# nRF9160_Thing_Plus.net
KiCad netlist of a schematic drawn in EAGLE
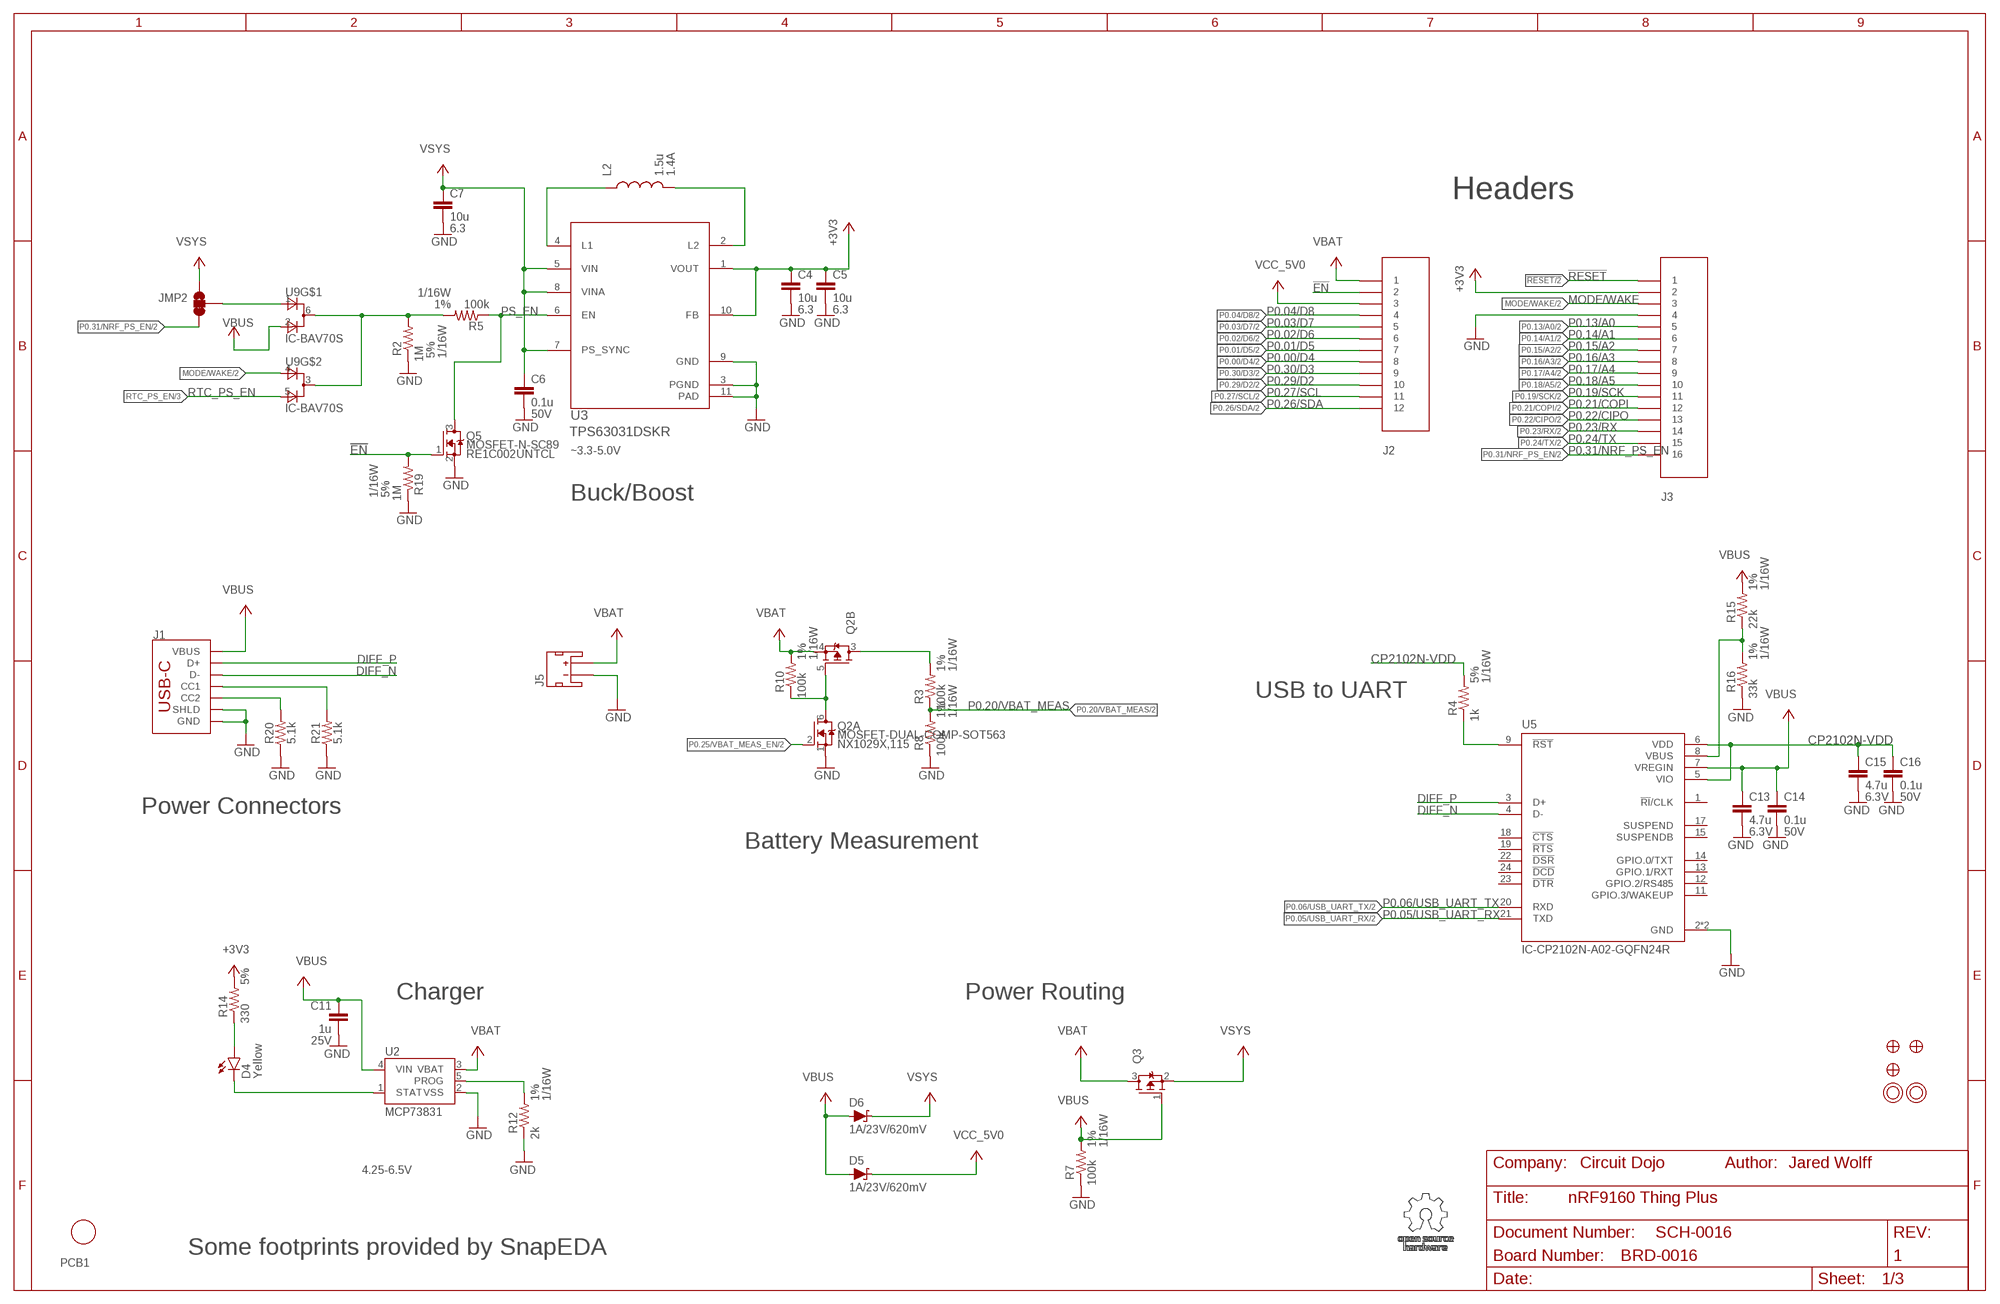
[diagram p0: schematic, sheet 1]
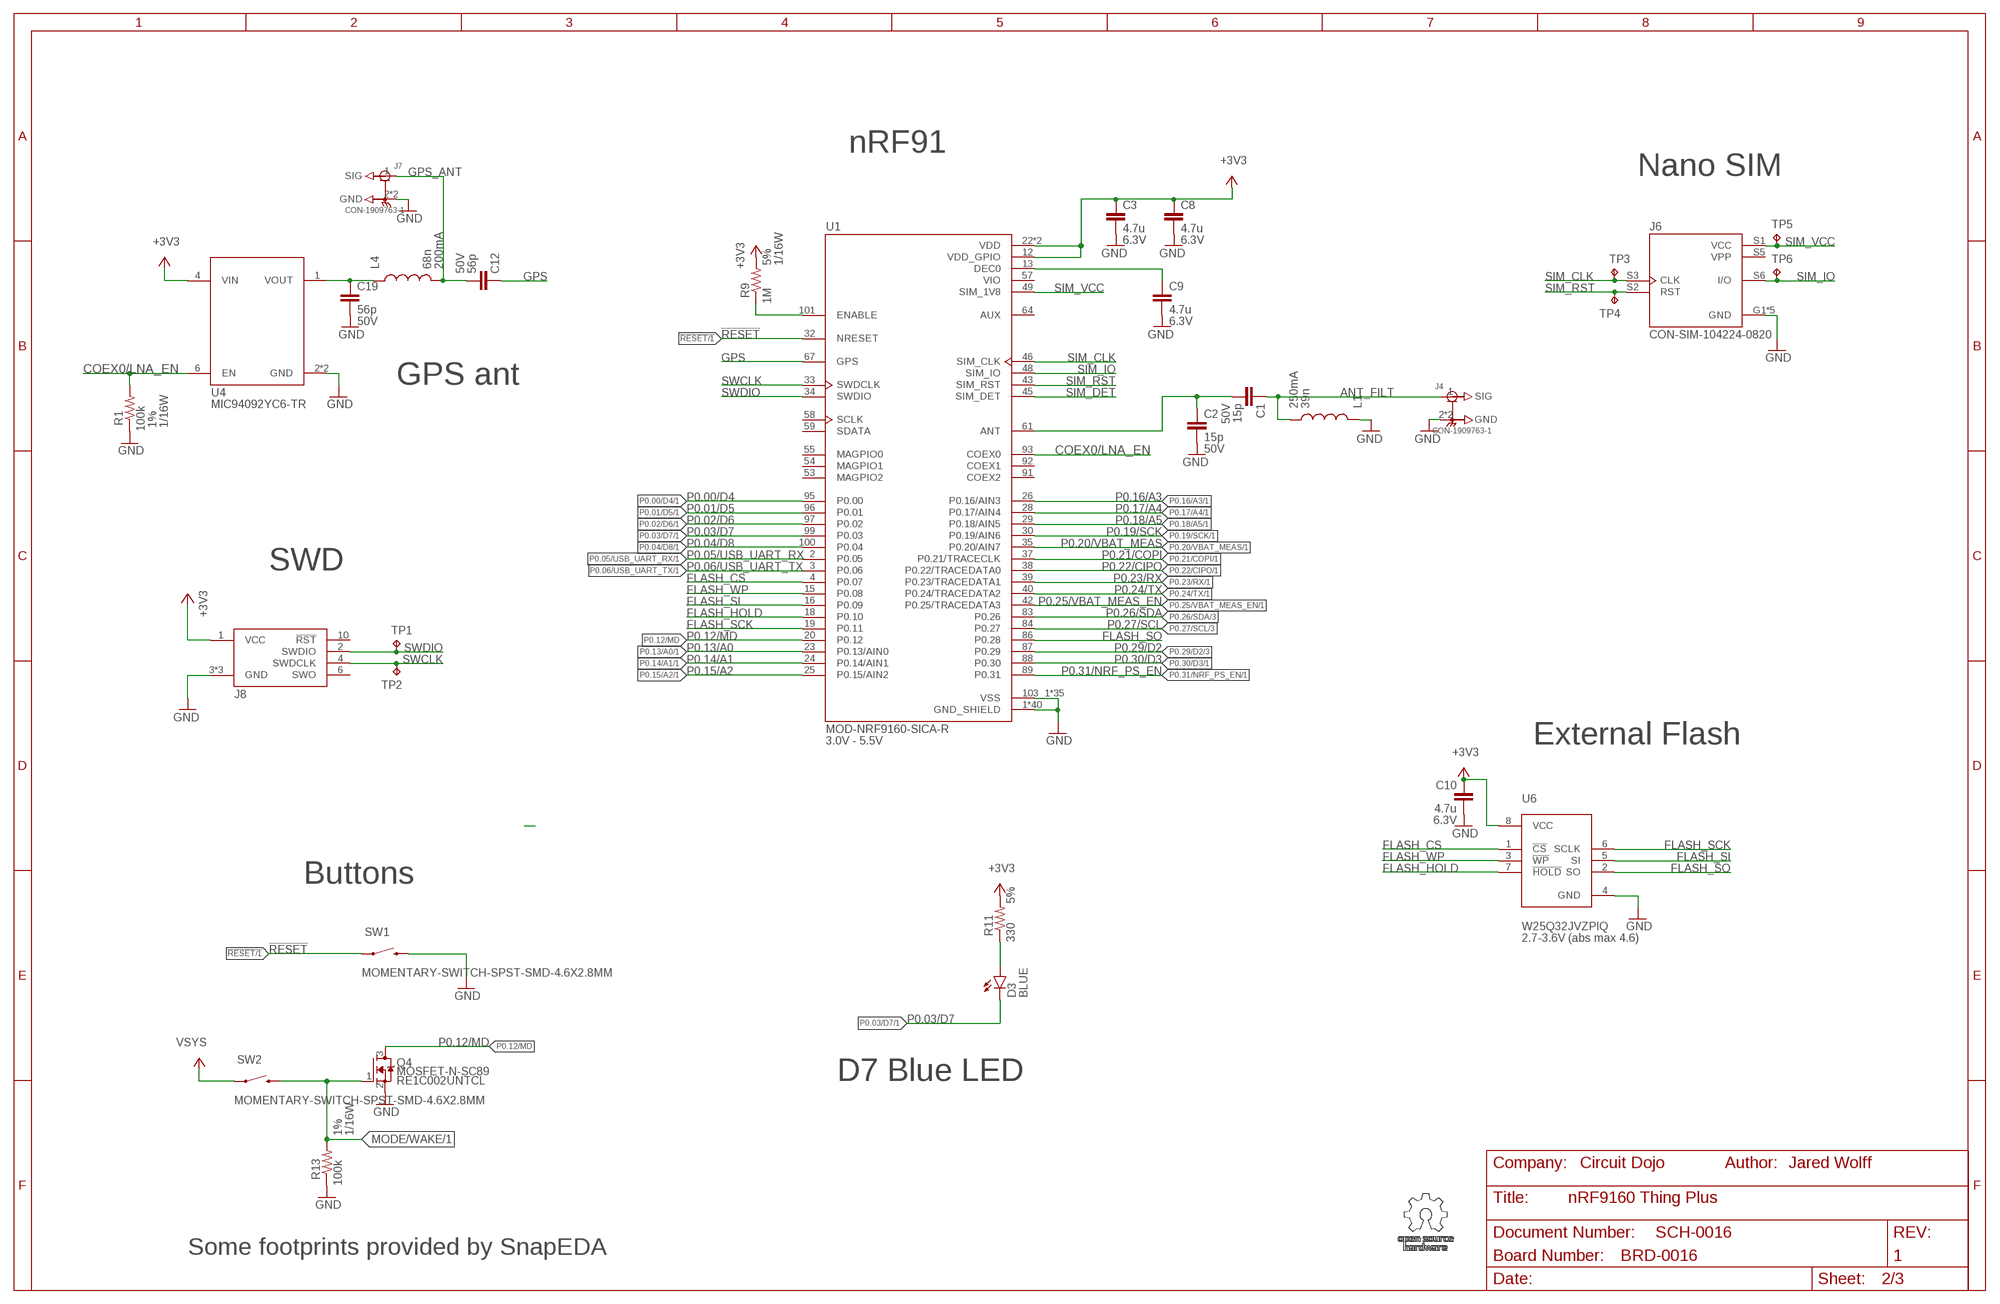
[diagram p1: schematic, sheet 2]
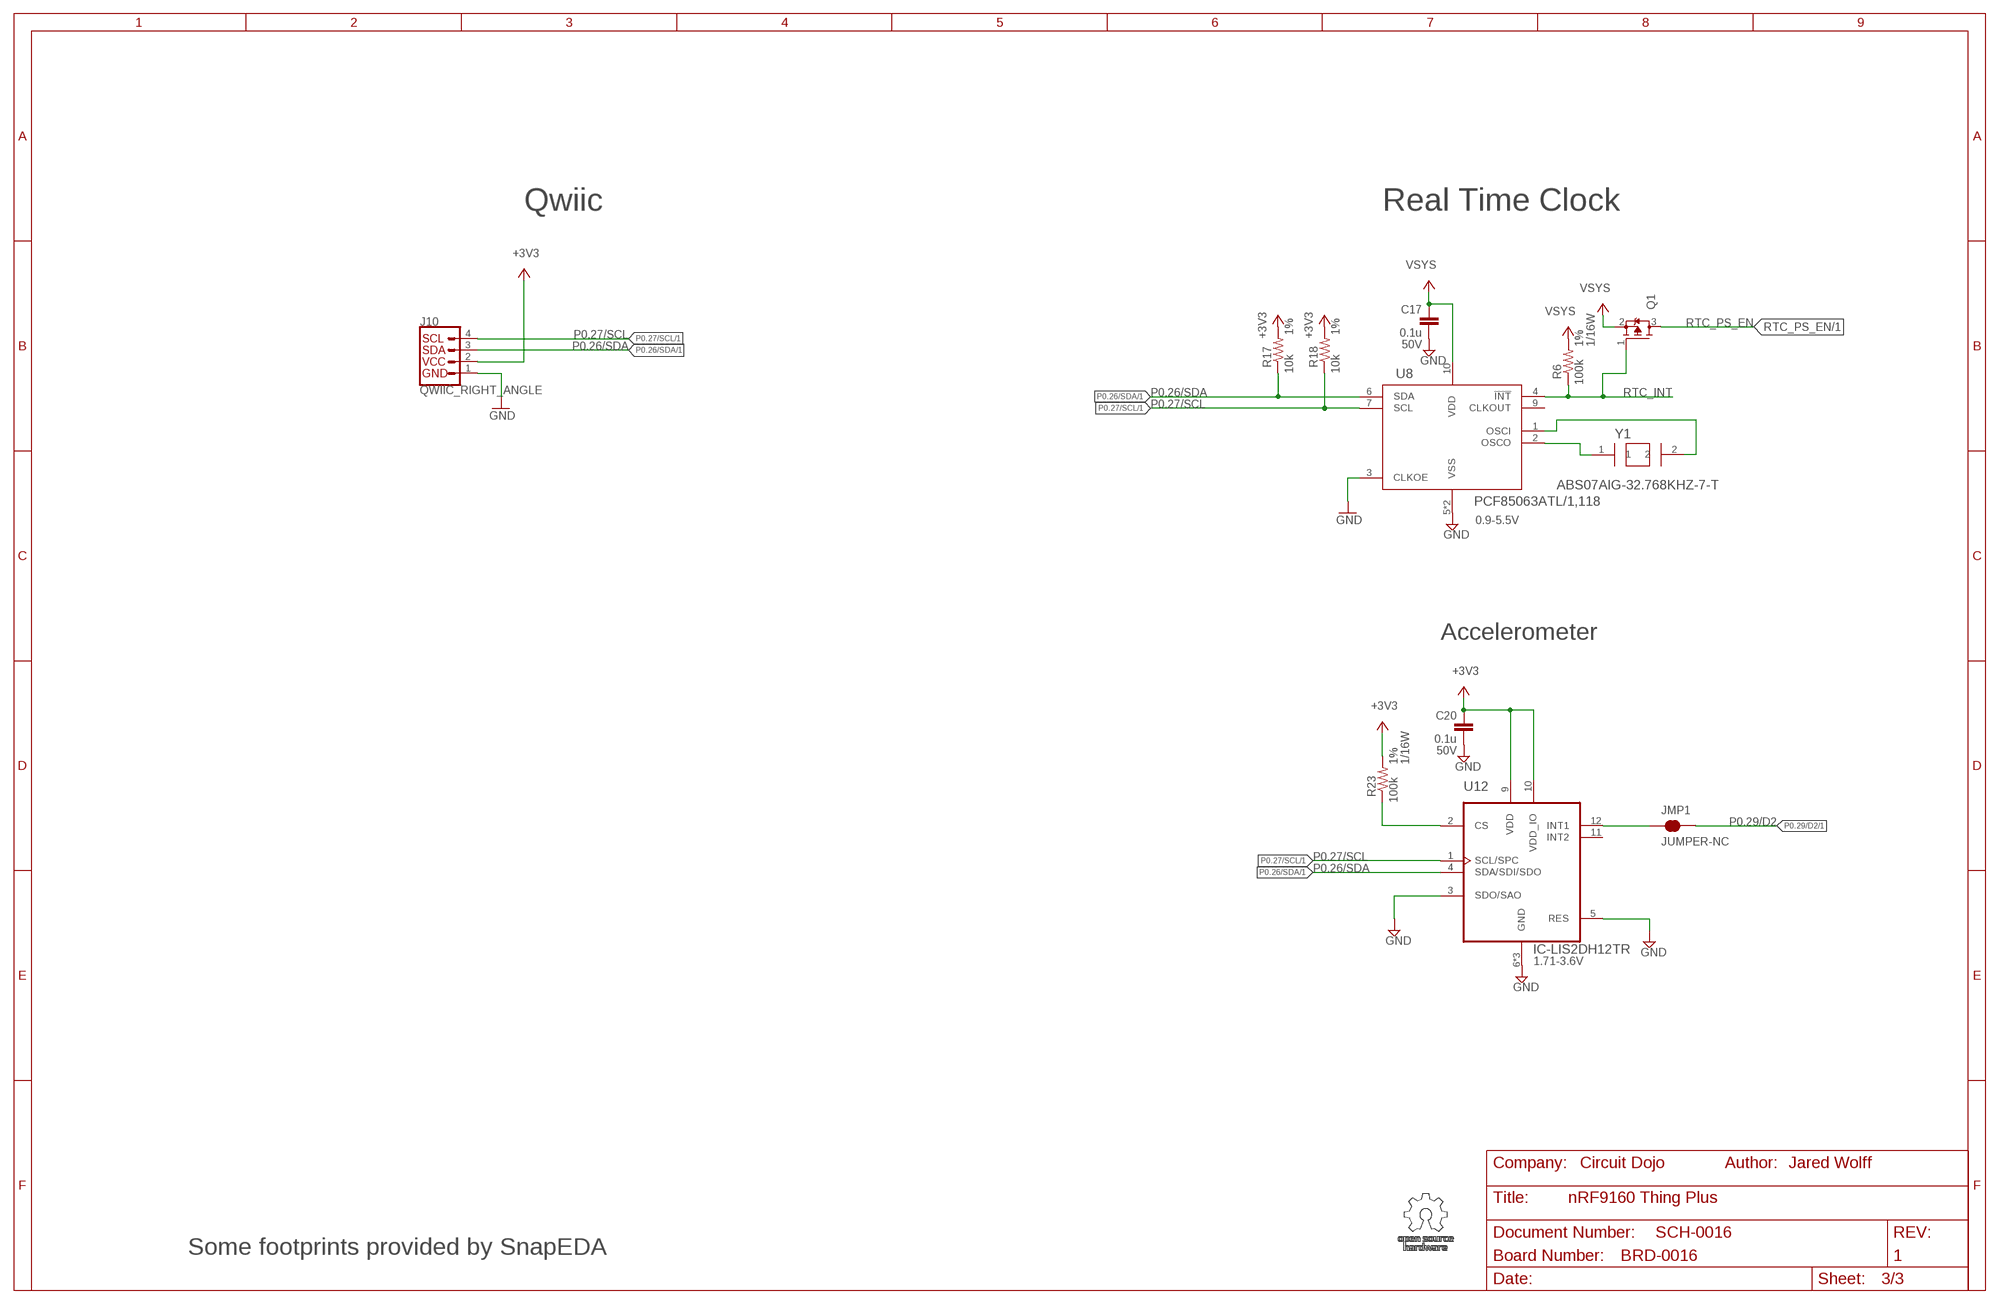
[diagram p2: schematic, sheet 3]

(export (version "E")
  (design (tool "Eeschema 10.0.6"))
  (components
    (comp (ref "C4")
      (value "10u")
      (footprint "eagle-import:C0603")
      (fields (field (name "MPN") "JMK107ABJ106MA-T") (field (name "VOLTHIGH") "6.3"))
      (libsource (lib "eagle-import") (part "CAP-0603-10U-6.3V"))
    )
    (comp (ref "C5")
      (value "10u")
      (footprint "eagle-import:C0603")
      (fields (field (name "MPN") "JMK107ABJ106MA-T") (field (name "VOLTHIGH") "6.3"))
      (libsource (lib "eagle-import") (part "CAP-0603-10U-6.3V"))
    )
    (comp (ref "C6")
      (value "0.1u")
      (footprint "eagle-import:CAPC1005X55N")
      (fields
        (field (name "MF") "Taiyo Yuden")
        (field (name "MPN") "UMK105BJ104KV-F")
        (field (name "VOLTHIGH") "50V")
      )
      (libsource (lib "eagle-import") (part "CAP-0402-0.1U-50V"))
    )
    (comp (ref "C7")
      (value "10u")
      (footprint "eagle-import:C0603")
      (fields (field (name "MPN") "JMK107ABJ106MA-T") (field (name "VOLTHIGH") "6.3"))
      (libsource (lib "eagle-import") (part "CAP-0603-10U-6.3V"))
    )
    (comp (ref "C11")
      (value "1u")
      (footprint "eagle-import:CAPC1005X55N")
      (fields
        (field (name "MF") "TDK")
        (field (name "MPN") "C1005X5R1E105M050BC")
        (field (name "VOLTHIGH") "25V")
      )
      (libsource (lib "eagle-import") (part "CAP-0402-1U-25V-1"))
    )
    (comp (ref "C13")
      (value "4.7u")
      (footprint "eagle-import:C0603")
      (fields (field (name "MPN") "JMK107BB7475MA-T") (field (name "VOLTHIGH") "6.3V"))
      (libsource (lib "eagle-import") (part "CAP-0603-4.7U-6.3V-2"))
    )
    (comp (ref "C14")
      (value "0.1u")
      (footprint "eagle-import:CAPC1005X55N")
      (fields
        (field (name "MF") "Taiyo Yuden")
        (field (name "MPN") "UMK105BJ104KV-F")
        (field (name "VOLTHIGH") "50V")
      )
      (libsource (lib "eagle-import") (part "CAP-0402-0.1U-50V"))
    )
    (comp (ref "C15")
      (value "4.7u")
      (footprint "eagle-import:C0603")
      (fields (field (name "MPN") "JMK107BB7475MA-T") (field (name "VOLTHIGH") "6.3V"))
      (libsource (lib "eagle-import") (part "CAP-0603-4.7U-6.3V-2"))
    )
    (comp (ref "C16")
      (value "0.1u")
      (footprint "eagle-import:CAPC1005X55N")
      (fields
        (field (name "MF") "Taiyo Yuden")
        (field (name "MPN") "UMK105BJ104KV-F")
        (field (name "VOLTHIGH") "50V")
      )
      (libsource (lib "eagle-import") (part "CAP-0402-0.1U-50V"))
    )
    (comp (ref "D4")
      (value "Yellow")
      (footprint "eagle-import:LED-0603")
      (libsource (lib "eagle-import") (part "LED-YELLOW0603"))
    )
    (comp (ref "D5")
      (value "1A/23V/620mV")
      (footprint "eagle-import:SOD-323")
      (libsource (lib "eagle-import") (part "DIODE-SCHOTTKY-BAT20J"))
    )
    (comp (ref "D6")
      (value "1A/23V/620mV")
      (footprint "eagle-import:SOD-323")
      (libsource (lib "eagle-import") (part "DIODE-SCHOTTKY-BAT20J"))
    )
    (comp (ref "J1")
      (value "USB Female C")
      (footprint "eagle-import:USB-C-16P-2LAYER-PADS")
      (libsource (lib "eagle-import") (part "USB_C_2-LAYER_PADS"))
    )
    (comp (ref "J2")
      (value "CON-HEADER-1X12-MALE-PIN")
      (footprint "eagle-import:CON-HEADER-1X12-MALE-PIN")
      (libsource (lib "eagle-import") (part "CON-HEADER-1X12-MALE-PIN"))
    )
    (comp (ref "J3")
      (value "CON-HEADER-1X16-MALE-PIN")
      (footprint "eagle-import:CON-HEADER-1X16-MALE-PIN")
      (libsource (lib "eagle-import") (part "CON-HEADER-1X16-MALE-PIN"))
    )
    (comp (ref "J5")
      (value "JST_2MM_MALE")
      (footprint "eagle-import:JST-2-SMD")
      (libsource (lib "eagle-import") (part "JST_2MM_MALE"))
    )
    (comp (ref "JMP2")
      (value "JUMPER-3/1")
      (footprint "eagle-import:JUMPER-ROUND-3-NO-R")
      (libsource (lib "eagle-import") (part "JUMPER-3/1"))
    )
    (comp (ref "L2")
      (value "1.5u")
      (footprint "eagle-import:IND-2P0X2P0X1P2")
      (fields (field (name "CURRENT") "1.4A") (field (name "MPN") "NRV2012T1R5NGF"))
      (libsource (lib "eagle-import") (part "IND-1.5U-1.4A-2X2"))
    )
    (comp (ref "PCB1")
      (value "PCB-NRF91-FEATHER")
      (footprint "eagle-import:PLACEHOLDER")
      (fields (field (name "MPN") "BRD-0015"))
      (libsource (lib "eagle-import") (part "PCB-NRF91-FEATHER"))
    )
    (comp (ref "Q2")
      (value "MOSFET-DUAL-COMP-SOT563")
      (footprint "eagle-import:SOT50P160X60-6N")
      (fields (field (name "MPN") "NX1029X,115"))
      (libsource (lib "eagle-import") (part "MOSFET-DUAL-COMP-SOT563"))
    )
    (comp (ref "Q3")
      (value "MOSFET-P-20V-4.7A-SOT23")
      (footprint "eagle-import:SOT23")
      (fields (field (name "MPN") "TSM500P02CX RFG"))
      (libsource (lib "eagle-import") (part "MOSFET-P-SOT23-20V-4.7A"))
    )
    (comp (ref "Q5")
      (value "MOSFET-N-SC89")
      (footprint "eagle-import:DIO_RB558WMF-L")
      (fields (field (name "MPN") "RE1C002UNTCL") (field (name "MF") "Rohm Semiconductor"))
      (libsource (lib "eagle-import") (part "MOSFET-N-SC89"))
    )
    (comp (ref "R2")
      (value "1M")
      (footprint "eagle-import:R0402-M")
      (fields
        (field (name "MPN") "RC0402JR-071ML")
        (field (name "POWER") "1/16W")
        (field (name "TOLERANCE") "5%")
      )
      (libsource (lib "eagle-import") (part "RES-0402-1M-5%"))
    )
    (comp (ref "R3")
      (value "100k")
      (footprint "eagle-import:R0402-M")
      (fields
        (field (name "MPN") "RC0402FR07100KL")
        (field (name "POWER") "1/16W")
        (field (name "TOLERANCE") "1%")
      )
      (libsource (lib "eagle-import") (part "RES-0402-100K-1%"))
    )
    (comp (ref "R4")
      (value "1k")
      (footprint "eagle-import:R0402-M")
      (fields
        (field (name "MPN") "RC0402JR-071KL")
        (field (name "POWER") "1/16W")
        (field (name "TOLERANCE") "5%")
      )
      (libsource (lib "eagle-import") (part "RES-0402-1K-5%"))
    )
    (comp (ref "R5")
      (value "100k")
      (footprint "eagle-import:R0402-M")
      (fields
        (field (name "MPN") "RC0402FR07100KL")
        (field (name "POWER") "1/16W")
        (field (name "TOLERANCE") "1%")
      )
      (libsource (lib "eagle-import") (part "RES-0402-100K-1%"))
    )
    (comp (ref "R7")
      (value "100k")
      (footprint "eagle-import:R0402-M")
      (fields
        (field (name "MPN") "RC0402FR07100KL")
        (field (name "POWER") "1/16W")
        (field (name "TOLERANCE") "1%")
      )
      (libsource (lib "eagle-import") (part "RES-0402-100K-1%"))
    )
    (comp (ref "R8")
      (value "100k")
      (footprint "eagle-import:R0402-M")
      (fields
        (field (name "MPN") "RC0402FR07100KL")
        (field (name "POWER") "1/16W")
        (field (name "TOLERANCE") "1%")
      )
      (libsource (lib "eagle-import") (part "RES-0402-100K-1%"))
    )
    (comp (ref "R10")
      (value "100k")
      (footprint "eagle-import:R0402-M")
      (fields
        (field (name "MPN") "RC0402FR07100KL")
        (field (name "POWER") "1/16W")
        (field (name "TOLERANCE") "1%")
      )
      (libsource (lib "eagle-import") (part "RES-0402-100K-1%"))
    )
    (comp (ref "R12")
      (value "2k")
      (footprint "eagle-import:R0402-M")
      (fields
        (field (name "MPN") "RC0402FR-072KL")
        (field (name "POWER") "1/16W")
        (field (name "TOLERANCE") "1%")
      )
      (libsource (lib "eagle-import") (part "RES-0402-2K-1%"))
    )
    (comp (ref "R14")
      (value "330")
      (footprint "eagle-import:R0402-M")
      (fields
        (field (name "MF") "Yageo")
        (field (name "MPN") "RC0402JR-07330RL")
        (field (name "TOLERANCE") "5%")
      )
      (libsource (lib "eagle-import") (part "RES-0402-330-5%"))
    )
    (comp (ref "R15")
      (value "22k")
      (footprint "eagle-import:R0402-M")
      (fields
        (field (name "MF") "Yageo")
        (field (name "MPN") "RC0402FR-0722KL")
        (field (name "POWER") "1/16W")
        (field (name "TOLERANCE") "1%")
      )
      (libsource (lib "eagle-import") (part "RES-0402-22K-1%"))
    )
    (comp (ref "R16")
      (value "33k")
      (footprint "eagle-import:R0402-M")
      (fields
        (field (name "MF") "Yageo")
        (field (name "MPN") "RC0402FR-0722KL")
        (field (name "POWER") "1/16W")
        (field (name "TOLERANCE") "1%")
      )
      (libsource (lib "eagle-import") (part "RES-0402-33K-1%"))
    )
    (comp (ref "R19")
      (value "1M")
      (footprint "eagle-import:R0402-M")
      (fields
        (field (name "MPN") "RC0402JR-071ML")
        (field (name "POWER") "1/16W")
        (field (name "TOLERANCE") "5%")
      )
      (libsource (lib "eagle-import") (part "RES-0402-1M-5%"))
    )
    (comp (ref "R20")
      (value "5.1k")
      (footprint "eagle-import:0402-TIGHT")
      (libsource (lib "eagle-import") (part "5.1KOHM-0402T-1/16W-1%"))
    )
    (comp (ref "R21")
      (value "5.1k")
      (footprint "eagle-import:0402-TIGHT")
      (libsource (lib "eagle-import") (part "5.1KOHM-0402T-1/16W-1%"))
    )
    (comp (ref "U$3")
      (value "FIDUCIAL-1MM")
      (footprint "eagle-import:FIDUCIAL-1MM")
      (libsource (lib "eagle-import") (part "FIDUCIAL-1MM"))
    )
    (comp (ref "U$4")
      (value "FIDUCIAL-1MM")
      (footprint "eagle-import:FIDUCIAL-1MM")
      (libsource (lib "eagle-import") (part "FIDUCIAL-1MM"))
    )
    (comp (ref "U$31")
      (value "MOUNTING-HOLE-2.5MM-PLATED")
      (footprint "eagle-import:MOUNTING-HOLE-2.5MM-PLATED")
      (libsource (lib "eagle-import") (part "MOUNTING-HOLE-2.5MM-PLATED"))
    )
    (comp (ref "U$32")
      (value "MOUNTING-HOLE-2.5MM-PLATED")
      (footprint "eagle-import:MOUNTING-HOLE-2.5MM-PLATED")
      (libsource (lib "eagle-import") (part "MOUNTING-HOLE-2.5MM-PLATED"))
    )
    (comp (ref "U$35")
      (value "FIDUCIAL-1MM")
      (footprint "eagle-import:FIDUCIAL-1MM")
      (libsource (lib "eagle-import") (part "FIDUCIAL-1MM"))
    )
    (comp (ref "U2")
      (value "MCP73831")
      (footprint "eagle-import:SOT23-5")
      (libsource (lib "eagle-import") (part "MCP73831"))
    )
    (comp (ref "U3")
      (value "IC-TPS63031DSKR")
      (footprint "eagle-import:DSK0010A")
      (fields (field (name "MF") "Texas Instruments") (field (name "MPN") "TPS63031DSKR"))
      (libsource (lib "eagle-import") (part "IC-TPS63031DSKR"))
    )
    (comp (ref "U5")
      (value "IC-CP2102N-A02-GQFN24R")
      (footprint "eagle-import:QFN50P400X400X80-25N")
      (fields (field (name "MF") "Silicon Labs") (field (name "MPN") "CP2102N-A02-GQFN24R"))
      (libsource (lib "eagle-import") (part "IC-CP2102N-A02-GQFN24R"))
    )
    (comp (ref "U9")
      (value "IC-BAV70S")
      (footprint "eagle-import:SOT363")
      (fields (field (name "MF") "Nexperia USA Inc.") (field (name "MPN") "BAV70S,115"))
      (libsource (lib "eagle-import") (part "IC-BAV70S"))
    )
    (comp (ref "C17")
      (value "0.1u")
      (footprint "eagle-import:CAPC1005X55N")
      (fields
        (field (name "MF") "Taiyo Yuden")
        (field (name "MPN") "UMK105BJ104KV-F")
        (field (name "VOLTHIGH") "50V")
      )
      (libsource (lib "eagle-import") (part "CAP-0402-0.1U-50V"))
    )
    (comp (ref "C20")
      (value "0.1u")
      (footprint "eagle-import:CAPC1005X55N")
      (fields
        (field (name "MF") "Taiyo Yuden")
        (field (name "MPN") "UMK105BJ104KV-F")
        (field (name "VOLTHIGH") "50V")
      )
      (libsource (lib "eagle-import") (part "CAP-0402-0.1U-50V"))
    )
    (comp (ref "J10")
      (value "QWIIC_RIGHT_ANGLE")
      (footprint "eagle-import:JST04_1MM_RA")
      (libsource (lib "eagle-import") (part "QWIIC_CONNECTORJS-1MM"))
    )
    (comp (ref "JMP1")
      (value "JUMPER-NC")
      (footprint "eagle-import:JUMPER-ROUND-NC")
      (libsource (lib "eagle-import") (part "JUMPER-NC"))
    )
    (comp (ref "Q1")
      (value "MOSFET-P-SC89")
      (footprint "eagle-import:DIO_RB558WMF-L")
      (fields (field (name "MPN") "RE1C001ZPTL"))
      (libsource (lib "eagle-import") (part "MOSFET-P-SC89"))
    )
    (comp (ref "R6")
      (value "100k")
      (footprint "eagle-import:R0402-M")
      (fields
        (field (name "MPN") "RC0402FR07100KL")
        (field (name "POWER") "1/16W")
        (field (name "TOLERANCE") "1%")
      )
      (libsource (lib "eagle-import") (part "RES-0402-100K-1%"))
    )
    (comp (ref "R17")
      (value "10k")
      (footprint "eagle-import:R0402-M")
      (fields (field (name "MPN") "RC0603FR-0710KL") (field (name "TOLERANCE") "1%"))
      (libsource (lib "eagle-import") (part "RES-0402-10K-1%"))
    )
    (comp (ref "R18")
      (value "10k")
      (footprint "eagle-import:R0402-M")
      (fields (field (name "MPN") "RC0603FR-0710KL") (field (name "TOLERANCE") "1%"))
      (libsource (lib "eagle-import") (part "RES-0402-10K-1%"))
    )
    (comp (ref "R23")
      (value "100k")
      (footprint "eagle-import:R0402-M")
      (fields
        (field (name "MPN") "RC0402FR07100KL")
        (field (name "POWER") "1/16W")
        (field (name "TOLERANCE") "1%")
      )
      (libsource (lib "eagle-import") (part "RES-0402-100K-1%"))
    )
    (comp (ref "U8")
      (value "IC-PCF85063ATL/1")
      (footprint "eagle-import:DFN10_2P7X2P7-L")
      (fields (field (name "MPN") "PCF85063ATL/1,118") (field (name "MF") "NXP"))
      (libsource (lib "eagle-import") (part "IC-PCF85063ATL/1"))
    )
    (comp (ref "U12")
      (value "IC-LIS2DH12TR")
      (footprint "eagle-import:PQFN50P200X200100-12N")
      (fields (field (name "MF") "STMicroelectronics") (field (name "MPN") "LIS2DH12TR"))
      (libsource (lib "eagle-import") (part "IC-LIS2DH12TR"))
    )
    (comp (ref "Y1")
      (value "XTAL-ABS07AIG-32.768KHZ-7-T")
      (footprint "eagle-import:XTAL320X150X90")
      (fields (field (name "MPN") "ABS07AIG-32.768KHZ-7-T") (field (name "MF") "Abracon"))
      (libsource (lib "eagle-import") (part "XTAL-ABS07AIG-32.768KHZ-7-T"))
    )
    (comp (ref "C1")
      (value "15p")
      (footprint "eagle-import:CAPC1005X55N")
      (fields
        (field (name "MF") "Yageo")
        (field (name "MPN") "CC0402JRNPO9BN150")
        (field (name "VOLTHIGH") "50V")
      )
      (libsource (lib "eagle-import") (part "CAP-0402-15P-50V"))
    )
    (comp (ref "C2")
      (value "15p")
      (footprint "eagle-import:CAPC1005X55N")
      (fields
        (field (name "MF") "Yageo")
        (field (name "MPN") "CC0402JRNPO9BN150")
        (field (name "VOLTHIGH") "50V")
      )
      (libsource (lib "eagle-import") (part "CAP-0402-15P-50V"))
    )
    (comp (ref "C3")
      (value "4.7u")
      (footprint "eagle-import:C0603")
      (fields (field (name "MPN") "JMK107BB7475MA-T") (field (name "VOLTHIGH") "6.3V"))
      (libsource (lib "eagle-import") (part "CAP-0603-4.7U-6.3V-2"))
    )
    (comp (ref "C8")
      (value "4.7u")
      (footprint "eagle-import:C0603")
      (fields (field (name "MPN") "JMK107BB7475MA-T") (field (name "VOLTHIGH") "6.3V"))
      (libsource (lib "eagle-import") (part "CAP-0603-4.7U-6.3V-2"))
    )
    (comp (ref "C9")
      (value "4.7u")
      (footprint "eagle-import:C0603")
      (fields (field (name "MPN") "JMK107BB7475MA-T") (field (name "VOLTHIGH") "6.3V"))
      (libsource (lib "eagle-import") (part "CAP-0603-4.7U-6.3V-2"))
    )
    (comp (ref "C10")
      (value "4.7u")
      (footprint "eagle-import:C0603")
      (fields (field (name "MPN") "JMK107BB7475MA-T") (field (name "VOLTHIGH") "6.3V"))
      (libsource (lib "eagle-import") (part "CAP-0603-4.7U-6.3V-2"))
    )
    (comp (ref "C12")
      (value "56p")
      (footprint "eagle-import:CAPC1005X55N")
      (fields
        (field (name "MF") "Kemet")
        (field (name "MPN") "C0402C560J5GACTU‎")
        (field (name "VOLTHIGH") "50V")
      )
      (libsource (lib "eagle-import") (part "CAP-0402-56PF-50V"))
    )
    (comp (ref "C19")
      (value "56p")
      (footprint "eagle-import:CAPC1005X55N")
      (fields
        (field (name "MF") "Kemet")
        (field (name "MPN") "C0402C560J5GACTU‎")
        (field (name "VOLTHIGH") "50V")
      )
      (libsource (lib "eagle-import") (part "CAP-0402-56PF-50V"))
    )
    (comp (ref "D3")
      (value "BLUE")
      (footprint "eagle-import:LED-0603")
      (libsource (lib "eagle-import") (part "LED-BLUE0603"))
    )
    (comp (ref "J4")
      (value "CON-1909763-1")
      (footprint "eagle-import:TE_1909763-1")
      (fields (field (name "MF") "TE Connectivity") (field (name "MPN") "1909763-1"))
      (libsource (lib "eagle-import") (part "CON-1909763-1"))
    )
    (comp (ref "J6")
      (value "CON-SIM-104224-0820")
      (footprint "eagle-import:MOLEX_104224-0820")
      (fields (field (name "MF") "Molex") (field (name "MPN") "104224-0820"))
      (libsource (lib "eagle-import") (part "CON-SIM-104224-0820"))
    )
    (comp (ref "J7")
      (value "CON-1909763-1")
      (footprint "eagle-import:TE_1909763-1")
      (fields (field (name "MF") "TE Connectivity") (field (name "MPN") "1909763-1"))
      (libsource (lib "eagle-import") (part "CON-1909763-1"))
    )
    (comp (ref "J8")
      (value "CON-FTSH-105-XX-X-DV")
      (footprint "eagle-import:SAMTEC_FTSH-105-XX-X-DV")
      (fields (field (name "MF") "Samtec") (field (name "MPN") "FTSH-105-01-F-DV-K"))
      (libsource (lib "eagle-import") (part "CON-FTSH-105-XX-X-DV"))
    )
    (comp (ref "L1")
      (value "39n")
      (footprint "eagle-import:IND0402_22N_TAI")
      (fields (field (name "CURRENT") "250mA") (field (name "MPN") "LQG15HN39NJ02D"))
      (libsource (lib "eagle-import") (part "IND-0402-39NH-250MA"))
    )
    (comp (ref "L4")
      (value "68n")
      (footprint "eagle-import:IND0402_22N_TAI")
      (fields (field (name "CURRENT") "200mA") (field (name "MPN") "LQG15HN68NH02D‎"))
      (libsource (lib "eagle-import") (part "IND-0402-68NH-200MA"))
    )
    (comp (ref "Q4")
      (value "MOSFET-N-SC89")
      (footprint "eagle-import:DIO_RB558WMF-L")
      (fields (field (name "MPN") "RE1C002UNTCL") (field (name "MF") "Rohm Semiconductor"))
      (libsource (lib "eagle-import") (part "MOSFET-N-SC89"))
    )
    (comp (ref "R1")
      (value "100k")
      (footprint "eagle-import:R0402-M")
      (fields
        (field (name "MPN") "RC0402FR07100KL")
        (field (name "POWER") "1/16W")
        (field (name "TOLERANCE") "1%")
      )
      (libsource (lib "eagle-import") (part "RES-0402-100K-1%"))
    )
    (comp (ref "R9")
      (value "1M")
      (footprint "eagle-import:R0402-M")
      (fields
        (field (name "MPN") "RC0402JR-071ML")
        (field (name "POWER") "1/16W")
        (field (name "TOLERANCE") "5%")
      )
      (libsource (lib "eagle-import") (part "RES-0402-1M-5%"))
    )
    (comp (ref "R11")
      (value "330")
      (footprint "eagle-import:R0402-M")
      (fields
        (field (name "MF") "Yageo")
        (field (name "MPN") "RC0402JR-07330RL")
        (field (name "TOLERANCE") "5%")
      )
      (libsource (lib "eagle-import") (part "RES-0402-330-5%"))
    )
    (comp (ref "R13")
      (value "100k")
      (footprint "eagle-import:R0402-M")
      (fields
        (field (name "MPN") "RC0402FR07100KL")
        (field (name "POWER") "1/16W")
        (field (name "TOLERANCE") "1%")
      )
      (libsource (lib "eagle-import") (part "RES-0402-100K-1%"))
    )
    (comp (ref "SW1")
      (value "MOMENTARY-SWITCH-SPST-SMD-4.6X2.8MM")
      (footprint "eagle-import:TACTILE_SWITCH_SMD_4.6X2.8MM")
      (libsource (lib "eagle-import") (part "MOMENTARY-SWITCH-SPST-SMD-4.6X2.8MM"))
    )
    (comp (ref "SW2")
      (value "MOMENTARY-SWITCH-SPST-SMD-4.6X2.8MM")
      (footprint "eagle-import:TACTILE_SWITCH_SMD_4.6X2.8MM")
      (libsource (lib "eagle-import") (part "MOMENTARY-SWITCH-SPST-SMD-4.6X2.8MM"))
    )
    (comp (ref "TP1")
      (value "TP-1SIDE-1P0")
      (footprint "eagle-import:TP-1P0")
      (libsource (lib "eagle-import") (part "TP-1SIDE-1P0"))
    )
    (comp (ref "TP2")
      (value "TP-1SIDE-1P0")
      (footprint "eagle-import:TP-1P0")
      (libsource (lib "eagle-import") (part "TP-1SIDE-1P0"))
    )
    (comp (ref "TP3")
      (value "TP-1SIDE-1P0")
      (footprint "eagle-import:TP-1P0")
      (libsource (lib "eagle-import") (part "TP-1SIDE-1P0"))
    )
    (comp (ref "TP4")
      (value "TP-1SIDE-1P0")
      (footprint "eagle-import:TP-1P0")
      (libsource (lib "eagle-import") (part "TP-1SIDE-1P0"))
    )
    (comp (ref "TP5")
      (value "TP-1SIDE-1P0")
      (footprint "eagle-import:TP-1P0")
      (libsource (lib "eagle-import") (part "TP-1SIDE-1P0"))
    )
    (comp (ref "TP6")
      (value "TP-1SIDE-1P0")
      (footprint "eagle-import:TP-1P0")
      (libsource (lib "eagle-import") (part "TP-1SIDE-1P0"))
    )
    (comp (ref "U1")
      (value "MOD-NRF9160-SICA-R")
      (footprint "eagle-import:NORDIC_NRF9160-SICA-R")
      (fields (field (name "MF") "Nordic Semiconductor") (field (name "MPN") "NRF9160-SICA-R"))
      (libsource (lib "eagle-import") (part "MOD-NRF9160-SICA-R"))
    )
    (comp (ref "U4")
      (value "POWER-SWITCH-MIC94092YC6")
      (footprint "eagle-import:SOT363")
      (fields (field (name "MPN") "MIC94092YC6-TR"))
      (libsource (lib "eagle-import") (part "POWER-SWITCH-MIC94092YC6"))
    )
    (comp (ref "U6")
      (value "FLASH-WSON")
      (footprint "eagle-import:WIN_ZP-8-L")
      (fields (field (name "MPN") "W25Q32JVZPIQ"))
      (libsource (lib "eagle-import") (part "FLASH-WSON-W25Q32JVZPIQ"))
    )
  )
  (nets
    (net (code "1") (name "+3V3") (class "Default")
      (node (ref "C10") (pin "1") (pinfunction "1_1") (pintype "passive"))
      (node (ref "C20") (pin "1") (pinfunction "1_1") (pintype "passive"))
      (node (ref "C3") (pin "1") (pinfunction "1_1") (pintype "passive"))
      (node (ref "C4") (pin "1") (pinfunction "1_1") (pintype "passive"))
      (node (ref "C5") (pin "1") (pinfunction "1_1") (pintype "passive"))
      (node (ref "C8") (pin "1") (pinfunction "1_1") (pintype "passive"))
      (node (ref "J10") (pin "2") (pinfunction "2_2") (pintype "power_in"))
      (node (ref "J3") (pin "2") (pinfunction "2_2") (pintype "bidirectional"))
      (node (ref "J8") (pin "1") (pinfunction "VCC_1") (pintype "bidirectional"))
      (node (ref "R11") (pin "2") (pinfunction "2_2") (pintype "passive"))
      (node (ref "R14") (pin "2") (pinfunction "2_2") (pintype "passive"))
      (node (ref "R17") (pin "2") (pinfunction "2_2") (pintype "passive"))
      (node (ref "R18") (pin "2") (pinfunction "2_2") (pintype "passive"))
      (node (ref "R23") (pin "2") (pinfunction "2_2") (pintype "passive"))
      (node (ref "R9") (pin "2") (pinfunction "2_2") (pintype "passive"))
      (node (ref "U1") (pin "102") (pinfunction "VDD_102") (pintype "power_in"))
      (node (ref "U1") (pin "12") (pinfunction "VDD_GPIO_12") (pintype "power_in"))
      (node (ref "U1") (pin "22") (pinfunction "VDD_22") (pintype "power_in"))
      (node (ref "U12") (pin "10") (pinfunction "VDD_IO_10") (pintype "power_in"))
      (node (ref "U12") (pin "9") (pinfunction "VDD_9") (pintype "power_in"))
      (node (ref "U3") (pin "1") (pinfunction "VOUT_1") (pintype "power_in"))
      (node (ref "U3") (pin "10") (pinfunction "FB_10") (pintype "input"))
      (node (ref "U4") (pin "4") (pinfunction "VIN_4") (pintype "power_in"))
      (node (ref "U6") (pin "8") (pinfunction "VCC_8") (pintype "bidirectional"))
    )
    (net (code "2") (name "ANT_FILT") (class "Default")
      (node (ref "C1") (pin "1") (pinfunction "1_1") (pintype "passive"))
      (node (ref "J4") (pin "1") (pinfunction "SIG_1") (pintype "passive"))
      (node (ref "L1") (pin "2") (pinfunction "2_2") (pintype "passive"))
    )
    (net (code "3") (name "COEX0{slash}LNA_EN") (class "Default")
      (node (ref "R1") (pin "2") (pinfunction "2_2") (pintype "passive"))
      (node (ref "U1") (pin "93") (pinfunction "COEX0_93") (pintype "bidirectional"))
      (node (ref "U4") (pin "6") (pinfunction "EN_6") (pintype "input"))
    )
    (net (code "4") (name "CP2102N-VDD") (class "Default")
      (node (ref "C15") (pin "1") (pinfunction "1_1") (pintype "passive"))
      (node (ref "C16") (pin "1") (pinfunction "1_1") (pintype "passive"))
      (node (ref "R4") (pin "2") (pinfunction "2_2") (pintype "passive"))
      (node (ref "U5") (pin "5") (pinfunction "VIO_5") (pintype "power_in"))
      (node (ref "U5") (pin "6") (pinfunction "VDD_6") (pintype "power_in"))
    )
    (net (code "5") (name "DIFF_N") (class "Default")
      (node (ref "J1") (pin "A7") (pinfunction "D-_A7") (pintype "bidirectional"))
      (node (ref "J1") (pin "B7") (pinfunction "D-_B7") (pintype "bidirectional"))
      (node (ref "U5") (pin "4") (pinfunction "D-_4") (pintype "bidirectional"))
    )
    (net (code "6") (name "DIFF_P") (class "Default")
      (node (ref "J1") (pin "A6") (pinfunction "D+_A6") (pintype "bidirectional"))
      (node (ref "J1") (pin "B6") (pinfunction "D+_B6") (pintype "bidirectional"))
      (node (ref "U5") (pin "3") (pinfunction "D+_3") (pintype "bidirectional"))
    )
    (net (code "7") (name "FLASH_CS") (class "Default")
      (node (ref "U1") (pin "4") (pinfunction "P0.07_4") (pintype "bidirectional"))
      (node (ref "U6") (pin "1") (pinfunction "~{CS}_1") (pintype "bidirectional"))
    )
    (net (code "8") (name "FLASH_HOLD") (class "Default")
      (node (ref "U1") (pin "18") (pinfunction "P0.10_18") (pintype "bidirectional"))
      (node (ref "U6") (pin "7") (pinfunction "~{HOLD}_7") (pintype "bidirectional"))
    )
    (net (code "9") (name "FLASH_SCK") (class "Default")
      (node (ref "U1") (pin "19") (pinfunction "P0.11_19") (pintype "bidirectional"))
      (node (ref "U6") (pin "6") (pinfunction "SCLK_6") (pintype "bidirectional"))
    )
    (net (code "10") (name "FLASH_SI") (class "Default")
      (node (ref "U1") (pin "16") (pinfunction "P0.09_16") (pintype "bidirectional"))
      (node (ref "U6") (pin "5") (pinfunction "SI_5") (pintype "bidirectional"))
    )
    (net (code "11") (name "FLASH_SO") (class "Default")
      (node (ref "U1") (pin "86") (pinfunction "P0.28_86") (pintype "bidirectional"))
      (node (ref "U6") (pin "2") (pinfunction "SO_2") (pintype "bidirectional"))
    )
    (net (code "12") (name "FLASH_WP") (class "Default")
      (node (ref "U1") (pin "15") (pinfunction "P0.08_15") (pintype "bidirectional"))
      (node (ref "U6") (pin "3") (pinfunction "~{WP}_3") (pintype "bidirectional"))
    )
    (net (code "13") (name "GND") (class "Default")
      (node (ref "C10") (pin "2") (pinfunction "2_2") (pintype "passive"))
      (node (ref "C11") (pin "2") (pinfunction "2_2") (pintype "passive"))
      (node (ref "C13") (pin "2") (pinfunction "2_2") (pintype "passive"))
      (node (ref "C14") (pin "2") (pinfunction "2_2") (pintype "passive"))
      (node (ref "C15") (pin "2") (pinfunction "2_2") (pintype "passive"))
      (node (ref "C16") (pin "2") (pinfunction "2_2") (pintype "passive"))
      (node (ref "C17") (pin "2") (pinfunction "2_2") (pintype "passive"))
      (node (ref "C19") (pin "2") (pinfunction "2_2") (pintype "passive"))
      (node (ref "C2") (pin "2") (pinfunction "2_2") (pintype "passive"))
      (node (ref "C20") (pin "2") (pinfunction "2_2") (pintype "passive"))
      (node (ref "C3") (pin "2") (pinfunction "2_2") (pintype "passive"))
      (node (ref "C4") (pin "2") (pinfunction "2_2") (pintype "passive"))
      (node (ref "C5") (pin "2") (pinfunction "2_2") (pintype "passive"))
      (node (ref "C6") (pin "2") (pinfunction "2_2") (pintype "passive"))
      (node (ref "C7") (pin "2") (pinfunction "2_2") (pintype "passive"))
      (node (ref "C8") (pin "2") (pinfunction "2_2") (pintype "passive"))
      (node (ref "C9") (pin "2") (pinfunction "2_2") (pintype "passive"))
      (node (ref "J1") (pin "GND") (pinfunction "GND_GND") (pintype "bidirectional"))
      (node (ref "J1") (pin "GND2") (pinfunction "GND_GND2") (pintype "bidirectional"))
      (node (ref "J1") (pin "SHLD1") (pinfunction "SHLD_SHLD1") (pintype "bidirectional"))
      (node (ref "J1") (pin "SHLD2") (pinfunction "SHLD_SHLD2") (pintype "bidirectional"))
      (node (ref "J1") (pin "SHLD3") (pinfunction "SHLD_SHLD3") (pintype "bidirectional"))
      (node (ref "J1") (pin "SHLD4") (pinfunction "SHLD_SHLD4") (pintype "bidirectional"))
      (node (ref "J10") (pin "1") (pinfunction "1_1") (pintype "power_in"))
      (node (ref "J3") (pin "4") (pinfunction "4_4") (pintype "bidirectional"))
      (node (ref "J4") (pin "2") (pinfunction "GND_2") (pintype "passive"))
      (node (ref "J4") (pin "3") (pinfunction "GND_3") (pintype "passive"))
      (node (ref "J5") (pin "1") (pinfunction "-_1") (pintype "bidirectional"))
      (node (ref "J6") (pin "G1") (pinfunction "GND_G1") (pintype "power_in"))
      (node (ref "J6") (pin "G2") (pinfunction "GND_G2") (pintype "power_in"))
      (node (ref "J6") (pin "G3") (pinfunction "GND_G3") (pintype "power_in"))
      (node (ref "J6") (pin "G4") (pinfunction "GND_G4") (pintype "power_in"))
      (node (ref "J6") (pin "S4") (pinfunction "GND_S4") (pintype "power_in"))
      (node (ref "J7") (pin "2") (pinfunction "GND_2") (pintype "passive"))
      (node (ref "J7") (pin "3") (pinfunction "GND_3") (pintype "passive"))
      (node (ref "J8") (pin "3") (pinfunction "GND_3") (pintype "bidirectional"))
      (node (ref "J8") (pin "5") (pinfunction "GND_5") (pintype "bidirectional"))
      (node (ref "J8") (pin "9") (pinfunction "GND_9") (pintype "bidirectional"))
      (node (ref "L1") (pin "1") (pinfunction "1_1") (pintype "passive"))
      (node (ref "Q2") (pin "1") (pinfunction "S_1") (pintype "bidirectional"))
      (node (ref "Q4") (pin "2") (pinfunction "S_2") (pintype "bidirectional"))
      (node (ref "Q5") (pin "2") (pinfunction "S_2") (pintype "bidirectional"))
      (node (ref "R1") (pin "1") (pinfunction "1_1") (pintype "passive"))
      (node (ref "R12") (pin "1") (pinfunction "1_1") (pintype "passive"))
      (node (ref "R13") (pin "1") (pinfunction "1_1") (pintype "passive"))
      (node (ref "R16") (pin "1") (pinfunction "1_1") (pintype "passive"))
      (node (ref "R19") (pin "1") (pinfunction "1_1") (pintype "passive"))
      (node (ref "R2") (pin "1") (pinfunction "1_1") (pintype "passive"))
      (node (ref "R20") (pin "1") (pinfunction "1_1") (pintype "passive"))
      (node (ref "R21") (pin "1") (pinfunction "1_1") (pintype "passive"))
      (node (ref "R7") (pin "1") (pinfunction "1_1") (pintype "passive"))
      (node (ref "R8") (pin "1") (pinfunction "1_1") (pintype "passive"))
      (node (ref "SW1") (pin "3") (pinfunction "2_3") (pintype "passive"))
      (node (ref "SW1") (pin "4") (pinfunction "2_4") (pintype "passive"))
      (node (ref "U1") (pin "1") (pinfunction "GND_SHIELD_1") (pintype "power_in"))
      (node (ref "U1") (pin "103_1") (pinfunction "VSS_103_1") (pintype "power_in"))
      (node (ref "U1") (pin "103_10") (pinfunction "VSS_103_10") (pintype "power_in"))
      (node (ref "U1") (pin "103_11") (pinfunction "VSS_103_11") (pintype "power_in"))
      (node (ref "U1") (pin "103_12") (pinfunction "VSS_103_12") (pintype "power_in"))
      (node (ref "U1") (pin "103_13") (pinfunction "VSS_103_13") (pintype "power_in"))
      (node (ref "U1") (pin "103_14") (pinfunction "VSS_103_14") (pintype "power_in"))
      (node (ref "U1") (pin "103_15") (pinfunction "VSS_103_15") (pintype "power_in"))
      (node (ref "U1") (pin "103_16") (pinfunction "VSS_103_16") (pintype "power_in"))
      (node (ref "U1") (pin "103_17") (pinfunction "VSS_103_17") (pintype "power_in"))
      (node (ref "U1") (pin "103_18") (pinfunction "VSS_103_18") (pintype "power_in"))
      (node (ref "U1") (pin "103_19") (pinfunction "VSS_103_19") (pintype "power_in"))
      (node (ref "U1") (pin "103_2") (pinfunction "VSS_103_2") (pintype "power_in"))
      (node (ref "U1") (pin "103_20") (pinfunction "VSS_103_20") (pintype "power_in"))
      (node (ref "U1") (pin "103_21") (pinfunction "VSS_103_21") (pintype "power_in"))
      (node (ref "U1") (pin "103_22") (pinfunction "VSS_103_22") (pintype "power_in"))
      (node (ref "U1") (pin "103_23") (pinfunction "VSS_103_23") (pintype "power_in"))
      (node (ref "U1") (pin "103_24") (pinfunction "VSS_103_24") (pintype "power_in"))
      (node (ref "U1") (pin "103_25") (pinfunction "VSS_103_25") (pintype "power_in"))
      (node (ref "U1") (pin "103_26") (pinfunction "VSS_103_26") (pintype "power_in"))
      (node (ref "U1") (pin "103_27") (pinfunction "VSS_103_27") (pintype "power_in"))
      (node (ref "U1") (pin "103_28") (pinfunction "VSS_103_28") (pintype "power_in"))
      (node (ref "U1") (pin "103_29") (pinfunction "VSS_103_29") (pintype "power_in"))
      (node (ref "U1") (pin "103_3") (pinfunction "VSS_103_3") (pintype "power_in"))
      (node (ref "U1") (pin "103_30") (pinfunction "VSS_103_30") (pintype "power_in"))
      (node (ref "U1") (pin "103_31") (pinfunction "VSS_103_31") (pintype "power_in"))
      (node (ref "U1") (pin "103_32") (pinfunction "VSS_103_32") (pintype "power_in"))
      (node (ref "U1") (pin "103_33") (pinfunction "VSS_103_33") (pintype "power_in"))
      (node (ref "U1") (pin "103_34") (pinfunction "VSS_103_34") (pintype "power_in"))
      (node (ref "U1") (pin "103_35") (pinfunction "VSS_103_35") (pintype "power_in"))
      (node (ref "U1") (pin "103_4") (pinfunction "VSS_103_4") (pintype "power_in"))
      (node (ref "U1") (pin "103_5") (pinfunction "VSS_103_5") (pintype "power_in"))
      (node (ref "U1") (pin "103_6") (pinfunction "VSS_103_6") (pintype "power_in"))
      (node (ref "U1") (pin "103_7") (pinfunction "VSS_103_7") (pintype "power_in"))
      (node (ref "U1") (pin "103_8") (pinfunction "VSS_103_8") (pintype "power_in"))
      (node (ref "U1") (pin "103_9") (pinfunction "VSS_103_9") (pintype "power_in"))
      (node (ref "U1") (pin "11") (pinfunction "GND_SHIELD_11") (pintype "power_in"))
      (node (ref "U1") (pin "14") (pinfunction "GND_SHIELD_14") (pintype "power_in"))
      (node (ref "U1") (pin "17") (pinfunction "GND_SHIELD_17") (pintype "power_in"))
      (node (ref "U1") (pin "21") (pinfunction "GND_SHIELD_21") (pintype "power_in"))
      (node (ref "U1") (pin "27") (pinfunction "GND_SHIELD_27") (pintype "power_in"))
      (node (ref "U1") (pin "31") (pinfunction "GND_SHIELD_31") (pintype "power_in"))
      (node (ref "U1") (pin "36") (pinfunction "GND_SHIELD_36") (pintype "power_in"))
      (node (ref "U1") (pin "41") (pinfunction "GND_SHIELD_41") (pintype "power_in"))
      (node (ref "U1") (pin "44") (pinfunction "GND_SHIELD_44") (pintype "power_in"))
      (node (ref "U1") (pin "47") (pinfunction "GND_SHIELD_47") (pintype "power_in"))
      (node (ref "U1") (pin "5") (pinfunction "GND_SHIELD_5") (pintype "power_in"))
      (node (ref "U1") (pin "50") (pinfunction "GND_SHIELD_50") (pintype "power_in"))
      (node (ref "U1") (pin "52") (pinfunction "GND_SHIELD_52") (pintype "power_in"))
      (node (ref "U1") (pin "56") (pinfunction "GND_SHIELD_56") (pintype "power_in"))
      (node (ref "U1") (pin "6") (pinfunction "GND_SHIELD_6") (pintype "power_in"))
      (node (ref "U1") (pin "60") (pinfunction "GND_SHIELD_60") (pintype "power_in"))
      (node (ref "U1") (pin "62") (pinfunction "GND_SHIELD_62") (pintype "power_in"))
      (node (ref "U1") (pin "63") (pinfunction "GND_SHIELD_63") (pintype "power_in"))
      (node (ref "U1") (pin "65") (pinfunction "GND_SHIELD_65") (pintype "power_in"))
      (node (ref "U1") (pin "66") (pinfunction "GND_SHIELD_66") (pintype "power_in"))
      (node (ref "U1") (pin "68") (pinfunction "GND_SHIELD_68") (pintype "power_in"))
      (node (ref "U1") (pin "69") (pinfunction "GND_SHIELD_69") (pintype "power_in"))
      (node (ref "U1") (pin "7") (pinfunction "GND_SHIELD_7") (pintype "power_in"))
      (node (ref "U1") (pin "72") (pinfunction "GND_SHIELD_72") (pintype "power_in"))
      (node (ref "U1") (pin "74") (pinfunction "GND_SHIELD_74") (pintype "power_in"))
      (node (ref "U1") (pin "75") (pinfunction "GND_SHIELD_75") (pintype "power_in"))
      (node (ref "U1") (pin "76") (pinfunction "GND_SHIELD_76") (pintype "power_in"))
      (node (ref "U1") (pin "77") (pinfunction "GND_SHIELD_77") (pintype "power_in"))
      (node (ref "U1") (pin "78") (pinfunction "GND_SHIELD_78") (pintype "power_in"))
      (node (ref "U1") (pin "79") (pinfunction "GND_SHIELD_79") (pintype "power_in"))
      (node (ref "U1") (pin "8") (pinfunction "GND_SHIELD_8") (pintype "power_in"))
      (node (ref "U1") (pin "80") (pinfunction "GND_SHIELD_80") (pintype "power_in"))
      (node (ref "U1") (pin "81") (pinfunction "GND_SHIELD_81") (pintype "power_in"))
      (node (ref "U1") (pin "82") (pinfunction "GND_SHIELD_82") (pintype "power_in"))
      (node (ref "U1") (pin "85") (pinfunction "GND_SHIELD_85") (pintype "power_in"))
      (node (ref "U1") (pin "9") (pinfunction "GND_SHIELD_9") (pintype "power_in"))
      (node (ref "U1") (pin "90") (pinfunction "GND_SHIELD_90") (pintype "power_in"))
      (node (ref "U1") (pin "94") (pinfunction "GND_SHIELD_94") (pintype "power_in"))
      (node (ref "U1") (pin "98") (pinfunction "GND_SHIELD_98") (pintype "power_in"))
      (node (ref "U12") (pin "3") (pinfunction "SDO/SAO_3") (pintype "bidirectional"))
      (node (ref "U12") (pin "5") (pinfunction "RES_5") (pintype "power_in"))
      (node (ref "U12") (pin "6") (pinfunction "GND_6") (pintype "power_in"))
      (node (ref "U12") (pin "7") (pinfunction "GND_7") (pintype "power_in"))
      (node (ref "U12") (pin "8") (pinfunction "GND_8") (pintype "power_in"))
      (node (ref "U2") (pin "2") (pinfunction "VSS_2") (pintype "power_in"))
      (node (ref "U3") (pin "11") (pinfunction "PAD_11") (pintype "power_in"))
      (node (ref "U3") (pin "3") (pinfunction "PGND_3") (pintype "power_in"))
      (node (ref "U3") (pin "9") (pinfunction "GND_9") (pintype "power_in"))
      (node (ref "U4") (pin "2") (pinfunction "GND_2") (pintype "power_in"))
      (node (ref "U4") (pin "5") (pinfunction "GND_5") (pintype "power_in"))
      (node (ref "U5") (pin "2") (pinfunction "GND_2") (pintype "power_in"))
      (node (ref "U5") (pin "25") (pinfunction "GND_25") (pintype "power_in"))
      (node (ref "U6") (pin "4") (pinfunction "GND_4") (pintype "bidirectional"))
      (node (ref "U8") (pin "11") (pinfunction "VSS_11") (pintype "power_in"))
      (node (ref "U8") (pin "3") (pinfunction "CLKOE_3") (pintype "input"))
      (node (ref "U8") (pin "5") (pinfunction "VSS_5") (pintype "power_in"))
    )
    (net (code "14") (name "GPS") (class "Default")
      (node (ref "C12") (pin "1") (pinfunction "1_1") (pintype "passive"))
      (node (ref "U1") (pin "67") (pinfunction "GPS_67") (pintype "input"))
    )
    (net (code "15") (name "GPS_ANT") (class "Default")
      (node (ref "C12") (pin "2") (pinfunction "2_2") (pintype "passive"))
      (node (ref "J7") (pin "1") (pinfunction "SIG_1") (pintype "passive"))
      (node (ref "L4") (pin "2") (pinfunction "2_2") (pintype "passive"))
    )
    (net (code "16") (name "MODE{slash}WAKE") (class "Default")
      (node (ref "J3") (pin "3") (pinfunction "3_3") (pintype "bidirectional"))
      (node (ref "Q4") (pin "1") (pinfunction "G_1") (pintype "bidirectional"))
      (node (ref "R13") (pin "2") (pinfunction "2_2") (pintype "passive"))
      (node (ref "SW2") (pin "3") (pinfunction "2_3") (pintype "passive"))
      (node (ref "SW2") (pin "4") (pinfunction "2_4") (pintype "passive"))
      (node (ref "U9") (pin "4") (pinfunction "A1_4") (pintype "passive"))
    )
    (net (code "17") (name "Net-(D3-PadA)") (class "Default")
      (node (ref "D3") (pin "A") (pinfunction "A_A") (pintype "passive"))
      (node (ref "R11") (pin "1") (pinfunction "1_1") (pintype "passive"))
    )
    (net (code "18") (name "Net-(D4-PadA)") (class "Default")
      (node (ref "D4") (pin "A") (pinfunction "A_A") (pintype "passive"))
      (node (ref "R14") (pin "1") (pinfunction "1_1") (pintype "passive"))
    )
    (net (code "19") (name "Net-(J1-CC1)") (class "Default")
      (node (ref "J1") (pin "A5") (pinfunction "CC1_A5") (pintype "bidirectional"))
      (node (ref "R21") (pin "2") (pinfunction "2_2") (pintype "passive"))
    )
    (net (code "20") (name "Net-(J1-CC2)") (class "Default")
      (node (ref "J1") (pin "B5") (pinfunction "CC2_B5") (pintype "bidirectional"))
      (node (ref "R20") (pin "2") (pinfunction "2_2") (pintype "passive"))
    )
    (net (code "21") (name "Net-(JMP1-1)") (class "Default")
      (node (ref "JMP1") (pin "P$1") (pinfunction "1_P$1") (pintype "passive"))
      (node (ref "U12") (pin "12") (pinfunction "INT1_12") (pintype "output"))
    )
    (net (code "22") (name "Net-(JMP2-2)") (class "Default")
      (node (ref "JMP2") (pin "P$2") (pinfunction "2_P$2") (pintype "passive"))
      (node (ref "U9") (pin "1") (pinfunction "A1_1") (pintype "passive"))
    )
    (net (code "23") (name "Net-(L2-1)") (class "Default")
      (node (ref "L2") (pin "P$1") (pinfunction "1_P$1") (pintype "passive"))
      (node (ref "U3") (pin "4") (pinfunction "L1_4") (pintype "passive"))
    )
    (net (code "24") (name "Net-(L2-2)") (class "Default")
      (node (ref "L2") (pin "P$2") (pinfunction "2_P$2") (pintype "passive"))
      (node (ref "U3") (pin "2") (pinfunction "L2_2") (pintype "passive"))
    )
    (net (code "25") (name "Net-(Q2A-D)") (class "Default")
      (node (ref "Q2") (pin "5") (pinfunction "G_5") (pintype "passive"))
      (node (ref "Q2") (pin "6") (pinfunction "D_6") (pintype "bidirectional"))
      (node (ref "R10") (pin "1") (pinfunction "1_1") (pintype "passive"))
    )
    (net (code "26") (name "Net-(Q2B-D)") (class "Default")
      (node (ref "Q2") (pin "3") (pinfunction "D_3") (pintype "passive"))
      (node (ref "R3") (pin "2") (pinfunction "2_2") (pintype "passive"))
    )
    (net (code "27") (name "Net-(U1-ANT)") (class "Default")
      (node (ref "C1") (pin "2") (pinfunction "2_2") (pintype "passive"))
      (node (ref "C2") (pin "1") (pinfunction "1_1") (pintype "passive"))
      (node (ref "U1") (pin "61") (pinfunction "ANT_61") (pintype "bidirectional"))
    )
    (net (code "28") (name "Net-(U1-DEC0)") (class "Default")
      (node (ref "C9") (pin "1") (pinfunction "1_1") (pintype "passive"))
      (node (ref "U1") (pin "13") (pinfunction "DEC0_13") (pintype "power_in"))
    )
    (net (code "29") (name "Net-(U1-ENABLE)") (class "Default")
      (node (ref "R9") (pin "1") (pinfunction "1_1") (pintype "passive"))
      (node (ref "U1") (pin "101") (pinfunction "ENABLE_101") (pintype "input"))
    )
    (net (code "30") (name "Net-(U2-PROG)") (class "Default")
      (node (ref "R12") (pin "2") (pinfunction "2_2") (pintype "passive"))
      (node (ref "U2") (pin "5") (pinfunction "PROG_5") (pintype "input"))
    )
    (net (code "31") (name "Net-(U2-STAT)") (class "Default")
      (node (ref "D4") (pin "C") (pinfunction "C_C") (pintype "passive"))
      (node (ref "U2") (pin "1") (pinfunction "STAT_1") (pintype "output"))
    )
    (net (code "32") (name "Net-(U4-VOUT)") (class "Default")
      (node (ref "C19") (pin "1") (pinfunction "1_1") (pintype "passive"))
      (node (ref "L4") (pin "1") (pinfunction "1_1") (pintype "passive"))
      (node (ref "U4") (pin "1") (pinfunction "VOUT_1") (pintype "power_in"))
    )
    (net (code "33") (name "Net-(U5-VBUS)") (class "Default")
      (node (ref "R15") (pin "1") (pinfunction "1_1") (pintype "passive"))
      (node (ref "R16") (pin "2") (pinfunction "2_2") (pintype "passive"))
      (node (ref "U5") (pin "8") (pinfunction "VBUS_8") (pintype "input"))
    )
    (net (code "34") (name "Net-(U5-~{RST})") (class "Default")
      (node (ref "R4") (pin "1") (pinfunction "1_1") (pintype "passive"))
      (node (ref "U5") (pin "9") (pinfunction "~{RST}_9") (pintype "bidirectional"))
    )
    (net (code "35") (name "Net-(U8-OSCI)") (class "Default")
      (node (ref "U8") (pin "1") (pinfunction "OSCI_1") (pintype "input"))
      (node (ref "Y1") (pin "2") (pinfunction "2_2") (pintype "passive"))
    )
    (net (code "36") (name "Net-(U8-OSCO)") (class "Default")
      (node (ref "U8") (pin "2") (pinfunction "OSCO_2") (pintype "output"))
      (node (ref "Y1") (pin "1") (pinfunction "1_1") (pintype "passive"))
    )
    (net (code "37") (name "Net-(U9A-C)") (class "Default")
      (node (ref "R2") (pin "2") (pinfunction "2_2") (pintype "passive"))
      (node (ref "R5") (pin "2") (pinfunction "2_2") (pintype "passive"))
      (node (ref "U9") (pin "3") (pinfunction "C_3") (pintype "passive"))
      (node (ref "U9") (pin "6") (pinfunction "C_6") (pintype "passive"))
    )
    (net (code "38") (name "Net-(U12-CS)") (class "Default")
      (node (ref "R23") (pin "1") (pinfunction "1_1") (pintype "passive"))
      (node (ref "U12") (pin "2") (pinfunction "CS_2") (pintype "input"))
    )
    (net (code "39") (name "P0.00{slash}D4") (class "Default")
      (node (ref "J2") (pin "8") (pinfunction "8_8") (pintype "bidirectional"))
      (node (ref "U1") (pin "95") (pinfunction "P0.00_95") (pintype "bidirectional"))
    )
    (net (code "40") (name "P0.01{slash}D5") (class "Default")
      (node (ref "J2") (pin "7") (pinfunction "7_7") (pintype "bidirectional"))
      (node (ref "U1") (pin "96") (pinfunction "P0.01_96") (pintype "bidirectional"))
    )
    (net (code "41") (name "P0.02{slash}D6") (class "Default")
      (node (ref "J2") (pin "6") (pinfunction "6_6") (pintype "bidirectional"))
      (node (ref "U1") (pin "97") (pinfunction "P0.02_97") (pintype "bidirectional"))
    )
    (net (code "42") (name "P0.03{slash}D7") (class "Default")
      (node (ref "D3") (pin "C") (pinfunction "C_C") (pintype "passive"))
      (node (ref "J2") (pin "5") (pinfunction "5_5") (pintype "bidirectional"))
      (node (ref "U1") (pin "99") (pinfunction "P0.03_99") (pintype "bidirectional"))
    )
    (net (code "43") (name "P0.04{slash}D8") (class "Default")
      (node (ref "J2") (pin "4") (pinfunction "4_4") (pintype "bidirectional"))
      (node (ref "U1") (pin "100") (pinfunction "P0.04_100") (pintype "bidirectional"))
    )
    (net (code "44") (name "P0.05{slash}USB_UART_RX") (class "Default")
      (node (ref "U1") (pin "2") (pinfunction "P0.05_2") (pintype "bidirectional"))
      (node (ref "U5") (pin "21") (pinfunction "TXD_21") (pintype "output"))
    )
    (net (code "45") (name "P0.06{slash}USB_UART_TX") (class "Default")
      (node (ref "U1") (pin "3") (pinfunction "P0.06_3") (pintype "bidirectional"))
      (node (ref "U5") (pin "20") (pinfunction "RXD_20") (pintype "input"))
    )
    (net (code "46") (name "P0.12{slash}MD") (class "Default")
      (node (ref "Q4") (pin "3") (pinfunction "D_3") (pintype "bidirectional"))
      (node (ref "U1") (pin "20") (pinfunction "P0.12_20") (pintype "bidirectional"))
    )
    (net (code "47") (name "P0.13{slash}A0") (class "Default")
      (node (ref "J3") (pin "5") (pinfunction "5_5") (pintype "bidirectional"))
      (node (ref "U1") (pin "23") (pinfunction "P0.13/AIN0_23") (pintype "bidirectional"))
    )
    (net (code "48") (name "P0.14{slash}A1") (class "Default")
      (node (ref "J3") (pin "6") (pinfunction "6_6") (pintype "bidirectional"))
      (node (ref "U1") (pin "24") (pinfunction "P0.14/AIN1_24") (pintype "bidirectional"))
    )
    (net (code "49") (name "P0.15{slash}A2") (class "Default")
      (node (ref "J3") (pin "7") (pinfunction "7_7") (pintype "bidirectional"))
      (node (ref "U1") (pin "25") (pinfunction "P0.15/AIN2_25") (pintype "bidirectional"))
    )
    (net (code "50") (name "P0.16{slash}A3") (class "Default")
      (node (ref "J3") (pin "8") (pinfunction "8_8") (pintype "bidirectional"))
      (node (ref "U1") (pin "26") (pinfunction "P0.16/AIN3_26") (pintype "bidirectional"))
    )
    (net (code "51") (name "P0.17{slash}A4") (class "Default")
      (node (ref "J3") (pin "9") (pinfunction "9_9") (pintype "bidirectional"))
      (node (ref "U1") (pin "28") (pinfunction "P0.17/AIN4_28") (pintype "bidirectional"))
    )
    (net (code "52") (name "P0.18{slash}A5") (class "Default")
      (node (ref "J3") (pin "10") (pinfunction "10_10") (pintype "bidirectional"))
      (node (ref "U1") (pin "29") (pinfunction "P0.18/AIN5_29") (pintype "bidirectional"))
    )
    (net (code "53") (name "P0.19{slash}SCK") (class "Default")
      (node (ref "J3") (pin "11") (pinfunction "11_11") (pintype "bidirectional"))
      (node (ref "U1") (pin "30") (pinfunction "P0.19/AIN6_30") (pintype "bidirectional"))
    )
    (net (code "54") (name "P0.20{slash}VBAT_MEAS") (class "Default")
      (node (ref "R3") (pin "1") (pinfunction "1_1") (pintype "passive"))
      (node (ref "R8") (pin "2") (pinfunction "2_2") (pintype "passive"))
      (node (ref "U1") (pin "35") (pinfunction "P0.20/AIN7_35") (pintype "bidirectional"))
    )
    (net (code "55") (name "P0.21{slash}COPI") (class "Default")
      (node (ref "J3") (pin "12") (pinfunction "12_12") (pintype "bidirectional"))
      (node (ref "U1") (pin "37") (pinfunction "P0.21/TRACECLK_37") (pintype "bidirectional"))
    )
    (net (code "56") (name "P0.22{slash}CIPO") (class "Default")
      (node (ref "J3") (pin "13") (pinfunction "13_13") (pintype "bidirectional"))
      (node (ref "U1") (pin "38") (pinfunction "P0.22/TRACEDATA0_38") (pintype "bidirectional"))
    )
    (net (code "57") (name "P0.23{slash}RX") (class "Default")
      (node (ref "J3") (pin "14") (pinfunction "14_14") (pintype "bidirectional"))
      (node (ref "U1") (pin "39") (pinfunction "P0.23/TRACEDATA1_39") (pintype "bidirectional"))
    )
    (net (code "58") (name "P0.24{slash}TX") (class "Default")
      (node (ref "J3") (pin "15") (pinfunction "15_15") (pintype "bidirectional"))
      (node (ref "U1") (pin "40") (pinfunction "P0.24/TRACEDATA2_40") (pintype "bidirectional"))
    )
    (net (code "59") (name "P0.25{slash}VBAT_MEAS_EN") (class "Default")
      (node (ref "Q2") (pin "2") (pinfunction "G_2") (pintype "bidirectional"))
      (node (ref "U1") (pin "42") (pinfunction "P0.25/TRACEDATA3_42") (pintype "bidirectional"))
    )
    (net (code "60") (name "P0.26{slash}SDA") (class "Default")
      (node (ref "J10") (pin "3") (pinfunction "3_3") (pintype "passive"))
      (node (ref "J2") (pin "12") (pinfunction "12_12") (pintype "bidirectional"))
      (node (ref "R17") (pin "1") (pinfunction "1_1") (pintype "passive"))
      (node (ref "U1") (pin "83") (pinfunction "P0.26_83") (pintype "bidirectional"))
      (node (ref "U12") (pin "4") (pinfunction "SDA/SDI/SDO_4") (pintype "bidirectional"))
      (node (ref "U8") (pin "6") (pinfunction "SDA_6") (pintype "bidirectional"))
    )
    (net (code "61") (name "P0.27{slash}SCL") (class "Default")
      (node (ref "J10") (pin "4") (pinfunction "4_4") (pintype "passive"))
      (node (ref "J2") (pin "11") (pinfunction "11_11") (pintype "bidirectional"))
      (node (ref "R18") (pin "1") (pinfunction "1_1") (pintype "passive"))
      (node (ref "U1") (pin "84") (pinfunction "P0.27_84") (pintype "bidirectional"))
      (node (ref "U12") (pin "1") (pinfunction "SCL/SPC_1") (pintype "bidirectional"))
      (node (ref "U8") (pin "7") (pinfunction "SCL_7") (pintype "input"))
    )
    (net (code "62") (name "P0.29{slash}D2") (class "Default")
      (node (ref "J2") (pin "10") (pinfunction "10_10") (pintype "bidirectional"))
      (node (ref "JMP1") (pin "P$2") (pinfunction "2_P$2") (pintype "passive"))
      (node (ref "U1") (pin "87") (pinfunction "P0.29_87") (pintype "bidirectional"))
    )
    (net (code "63") (name "P0.30{slash}D3") (class "Default")
      (node (ref "J2") (pin "9") (pinfunction "9_9") (pintype "bidirectional"))
      (node (ref "U1") (pin "88") (pinfunction "P0.30_88") (pintype "bidirectional"))
    )
    (net (code "64") (name "P0.31{slash}NRF_PS_EN") (class "Default")
      (node (ref "J3") (pin "16") (pinfunction "16_16") (pintype "bidirectional"))
      (node (ref "JMP2") (pin "P$3") (pinfunction "3_P$3") (pintype "passive"))
      (node (ref "U1") (pin "89") (pinfunction "P0.31_89") (pintype "bidirectional"))
    )
    (net (code "65") (name "PS_EN") (class "Default")
      (node (ref "Q5") (pin "3") (pinfunction "D_3") (pintype "bidirectional"))
      (node (ref "R5") (pin "1") (pinfunction "1_1") (pintype "passive"))
      (node (ref "U3") (pin "6") (pinfunction "EN_6") (pintype "input"))
    )
    (net (code "66") (name "RTC_INT") (class "Default")
      (node (ref "Q1") (pin "1") (pinfunction "G_1") (pintype "passive"))
      (node (ref "R6") (pin "1") (pinfunction "1_1") (pintype "passive"))
      (node (ref "U8") (pin "4") (pinfunction "~{INT}_4") (pintype "output"))
    )
    (net (code "67") (name "RTC_PS_EN") (class "Default")
      (node (ref "Q1") (pin "3") (pinfunction "D_3") (pintype "passive"))
      (node (ref "U9") (pin "5") (pinfunction "A2_5") (pintype "passive"))
    )
    (net (code "68") (name "SIM_CLK") (class "Default")
      (node (ref "J6") (pin "S3") (pinfunction "CLK_S3") (pintype "input"))
      (node (ref "TP3") (pin "TP") (pinfunction "TP_TP") (pintype "input"))
      (node (ref "U1") (pin "46") (pinfunction "SIM_CLK_46") (pintype "bidirectional"))
    )
    (net (code "69") (name "SIM_DET") (class "Default")
      (node (ref "U1") (pin "45") (pinfunction "SIM_DET_45") (pintype "bidirectional"))
    )
    (net (code "70") (name "SIM_IO") (class "Default")
      (node (ref "J6") (pin "S6") (pinfunction "I/O_S6") (pintype "bidirectional"))
      (node (ref "TP6") (pin "TP") (pinfunction "TP_TP") (pintype "input"))
      (node (ref "U1") (pin "48") (pinfunction "SIM_IO_48") (pintype "bidirectional"))
    )
    (net (code "71") (name "SIM_RST") (class "Default")
      (node (ref "J6") (pin "S2") (pinfunction "RST_S2") (pintype "input"))
      (node (ref "TP4") (pin "TP") (pinfunction "TP_TP") (pintype "input"))
      (node (ref "U1") (pin "43") (pinfunction "SIM_RST_43") (pintype "bidirectional"))
    )
    (net (code "72") (name "SIM_VCC") (class "Default")
      (node (ref "J6") (pin "S1") (pinfunction "VCC_S1") (pintype "power_in"))
      (node (ref "TP5") (pin "TP") (pinfunction "TP_TP") (pintype "input"))
      (node (ref "U1") (pin "49") (pinfunction "SIM_1V8_49") (pintype "power_in"))
    )
    (net (code "73") (name "SWCLK") (class "Default")
      (node (ref "J8") (pin "4") (pinfunction "SWDCLK_4") (pintype "bidirectional"))
      (node (ref "TP2") (pin "TP") (pinfunction "TP_TP") (pintype "input"))
      (node (ref "U1") (pin "33") (pinfunction "SWDCLK_33") (pintype "input"))
    )
    (net (code "74") (name "SWDIO") (class "Default")
      (node (ref "J8") (pin "2") (pinfunction "SWDIO_2") (pintype "bidirectional"))
      (node (ref "TP1") (pin "TP") (pinfunction "TP_TP") (pintype "input"))
      (node (ref "U1") (pin "34") (pinfunction "SWDIO_34") (pintype "bidirectional"))
    )
    (net (code "75") (name "VBAT") (class "Default")
      (node (ref "J2") (pin "1") (pinfunction "1_1") (pintype "bidirectional"))
      (node (ref "J5") (pin "2") (pinfunction "+_2") (pintype "bidirectional"))
      (node (ref "Q2") (pin "4") (pinfunction "S_4") (pintype "passive"))
      (node (ref "Q3") (pin "3") (pinfunction "D_3") (pintype "passive"))
      (node (ref "R10") (pin "2") (pinfunction "2_2") (pintype "passive"))
      (node (ref "U2") (pin "3") (pinfunction "VBAT_3") (pintype "power_in"))
    )
    (net (code "76") (name "VBUS") (class "Default")
      (node (ref "C11") (pin "1") (pinfunction "1_1") (pintype "passive"))
      (node (ref "C13") (pin "1") (pinfunction "1_1") (pintype "passive"))
      (node (ref "C14") (pin "1") (pinfunction "1_1") (pintype "passive"))
      (node (ref "D5") (pin "A") (pinfunction "A_A") (pintype "passive"))
      (node (ref "D6") (pin "A") (pinfunction "A_A") (pintype "passive"))
      (node (ref "J1") (pin "VBUS1") (pinfunction "VBUS_VBUS1") (pintype "bidirectional"))
      (node (ref "J1") (pin "VBUS2") (pinfunction "VBUS_VBUS2") (pintype "bidirectional"))
      (node (ref "Q3") (pin "1") (pinfunction "G_1") (pintype "passive"))
      (node (ref "R15") (pin "2") (pinfunction "2_2") (pintype "passive"))
      (node (ref "R7") (pin "2") (pinfunction "2_2") (pintype "passive"))
      (node (ref "U2") (pin "4") (pinfunction "VIN_4") (pintype "power_in"))
      (node (ref "U5") (pin "7") (pinfunction "VREGIN_7") (pintype "input"))
      (node (ref "U9") (pin "2") (pinfunction "A2_2") (pintype "passive"))
    )
    (net (code "77") (name "VCC_5V0") (class "Default")
      (node (ref "D5") (pin "C") (pinfunction "C_C") (pintype "passive"))
      (node (ref "J2") (pin "3") (pinfunction "3_3") (pintype "bidirectional"))
    )
    (net (code "78") (name "VIO") (class "Default")
      (node (ref "U1") (pin "57") (pinfunction "VIO_57") (pintype "power_in"))
    )
    (net (code "79") (name "VPP") (class "Default")
      (node (ref "J6") (pin "S5") (pinfunction "VPP_S5") (pintype "power_in"))
    )
    (net (code "80") (name "VSYS") (class "Default")
      (node (ref "C17") (pin "1") (pinfunction "1_1") (pintype "passive"))
      (node (ref "C6") (pin "1") (pinfunction "1_1") (pintype "passive"))
      (node (ref "C7") (pin "1") (pinfunction "1_1") (pintype "passive"))
      (node (ref "D6") (pin "C") (pinfunction "C_C") (pintype "passive"))
      (node (ref "JMP2") (pin "P$1") (pinfunction "1_P$1") (pintype "passive"))
      (node (ref "Q1") (pin "2") (pinfunction "S_2") (pintype "passive"))
      (node (ref "Q3") (pin "2") (pinfunction "S_2") (pintype "passive"))
      (node (ref "R6") (pin "2") (pinfunction "2_2") (pintype "passive"))
      (node (ref "SW2") (pin "1") (pinfunction "1_1") (pintype "passive"))
      (node (ref "SW2") (pin "2") (pinfunction "1_2") (pintype "passive"))
      (node (ref "U3") (pin "5") (pinfunction "VIN_5") (pintype "power_in"))
      (node (ref "U3") (pin "7") (pinfunction "PS_SYNC_7") (pintype "input"))
      (node (ref "U3") (pin "8") (pinfunction "VINA_8") (pintype "power_in"))
      (node (ref "U8") (pin "10") (pinfunction "VDD_10") (pintype "power_in"))
    )
    (net (code "81") (name "unconnected-(J5-PAD1-PadNC1)") (class "Default")
      (node (ref "J5") (pin "NC1") (pinfunction "PAD1_NC1") (pintype "bidirectional"))
    )
    (net (code "82") (name "unconnected-(J5-PAD2-PadNC2)") (class "Default")
      (node (ref "J5") (pin "NC2") (pinfunction "PAD2_NC2") (pintype "bidirectional"))
    )
    (net (code "83") (name "unconnected-(J8-SWO-Pad6)") (class "Default")
      (node (ref "J8") (pin "6") (pinfunction "SWO_6") (pintype "bidirectional"))
    )
    (net (code "84") (name "unconnected-(J8-~{RST}-Pad10)") (class "Default")
      (node (ref "J8") (pin "10") (pinfunction "~{RST}_10") (pintype "bidirectional"))
    )
    (net (code "85") (name "unconnected-(U1-AUX-Pad64)") (class "Default")
      (node (ref "U1") (pin "64") (pinfunction "AUX_64") (pintype "output"))
    )
    (net (code "86") (name "unconnected-(U1-COEX1-Pad92)") (class "Default")
      (node (ref "U1") (pin "92") (pinfunction "COEX1_92") (pintype "bidirectional"))
    )
    (net (code "87") (name "unconnected-(U1-COEX2-Pad91)") (class "Default")
      (node (ref "U1") (pin "91") (pinfunction "COEX2_91") (pintype "bidirectional"))
    )
    (net (code "88") (name "unconnected-(U1-MAGPIO0-Pad55)") (class "Default")
      (node (ref "U1") (pin "55") (pinfunction "MAGPIO0_55") (pintype "bidirectional"))
    )
    (net (code "89") (name "unconnected-(U1-MAGPIO1-Pad54)") (class "Default")
      (node (ref "U1") (pin "54") (pinfunction "MAGPIO1_54") (pintype "bidirectional"))
    )
    (net (code "90") (name "unconnected-(U1-MAGPIO2-Pad53)") (class "Default")
      (node (ref "U1") (pin "53") (pinfunction "MAGPIO2_53") (pintype "bidirectional"))
    )
    (net (code "91") (name "unconnected-(U1-SCLK-Pad58)") (class "Default")
      (node (ref "U1") (pin "58") (pinfunction "SCLK_58") (pintype "bidirectional"))
    )
    (net (code "92") (name "unconnected-(U1-SDATA-Pad59)") (class "Default")
      (node (ref "U1") (pin "59") (pinfunction "SDATA_59") (pintype "bidirectional"))
    )
    (net (code "93") (name "unconnected-(U5-GPIO.0{slash}TXT-Pad14)") (class "Default")
      (node (ref "U5") (pin "14") (pinfunction "GPIO.0/TXT_14") (pintype "bidirectional"))
    )
    (net (code "94") (name "unconnected-(U5-GPIO.1{slash}RXT-Pad13)") (class "Default")
      (node (ref "U5") (pin "13") (pinfunction "GPIO.1/RXT_13") (pintype "bidirectional"))
    )
    (net (code "95") (name "unconnected-(U5-GPIO.2{slash}RS485-Pad12)") (class "Default")
      (node (ref "U5") (pin "12") (pinfunction "GPIO.2/RS485_12") (pintype "bidirectional"))
    )
    (net (code "96") (name "unconnected-(U5-GPIO.3{slash}WAKEUP-Pad11)") (class "Default")
      (node (ref "U5") (pin "11") (pinfunction "GPIO.3/WAKEUP_11") (pintype "bidirectional"))
    )
    (net (code "97") (name "unconnected-(U5-SUSPEND-Pad17)") (class "Default")
      (node (ref "U5") (pin "17") (pinfunction "SUSPEND_17") (pintype "output"))
    )
    (net (code "98") (name "unconnected-(U5-SUSPENDB-Pad15)") (class "Default")
      (node (ref "U5") (pin "15") (pinfunction "SUSPENDB_15") (pintype "output"))
    )
    (net (code "99") (name "unconnected-(U5-~{CTS}-Pad18)") (class "Default")
      (node (ref "U5") (pin "18") (pinfunction "~{CTS}_18") (pintype "input"))
    )
    (net (code "100") (name "unconnected-(U5-~{DCD}-Pad24)") (class "Default")
      (node (ref "U5") (pin "24") (pinfunction "~{DCD}_24") (pintype "input"))
    )
    (net (code "101") (name "unconnected-(U5-~{DSR}-Pad22)") (class "Default")
      (node (ref "U5") (pin "22") (pinfunction "~{DSR}_22") (pintype "input"))
    )
    (net (code "102") (name "unconnected-(U5-~{DTR}-Pad23)") (class "Default")
      (node (ref "U5") (pin "23") (pinfunction "~{DTR}_23") (pintype "output"))
    )
    (net (code "103") (name "unconnected-(U5-~{RI}{slash}CLK-Pad1)") (class "Default")
      (node (ref "U5") (pin "1") (pinfunction "~{RI}/CLK_1") (pintype "bidirectional"))
    )
    (net (code "104") (name "unconnected-(U5-~{RTS}-Pad19)") (class "Default")
      (node (ref "U5") (pin "19") (pinfunction "~{RTS}_19") (pintype "output"))
    )
    (net (code "105") (name "unconnected-(U8-CLKOUT-Pad9)") (class "Default")
      (node (ref "U8") (pin "9") (pinfunction "CLKOUT_9") (pintype "output"))
    )
    (net (code "106") (name "unconnected-(U12-INT2-Pad11)") (class "Default")
      (node (ref "U12") (pin "11") (pinfunction "INT2_11") (pintype "output"))
    )
    (net (code "107") (name "~{EN}") (class "Default")
      (node (ref "J2") (pin "2") (pinfunction "2_2") (pintype "bidirectional"))
      (node (ref "Q5") (pin "1") (pinfunction "G_1") (pintype "bidirectional"))
      (node (ref "R19") (pin "2") (pinfunction "2_2") (pintype "passive"))
    )
    (net (code "108") (name "~{RESET}") (class "Default")
      (node (ref "J3") (pin "1") (pinfunction "1_1") (pintype "bidirectional"))
      (node (ref "SW1") (pin "1") (pinfunction "1_1") (pintype "passive"))
      (node (ref "SW1") (pin "2") (pinfunction "1_2") (pintype "passive"))
      (node (ref "U1") (pin "32") (pinfunction "NRESET_32") (pintype "input"))
    )
  )
)
